# ltk-hall_main.net
KiCad netlist of a schematic drawn in Altium Designer
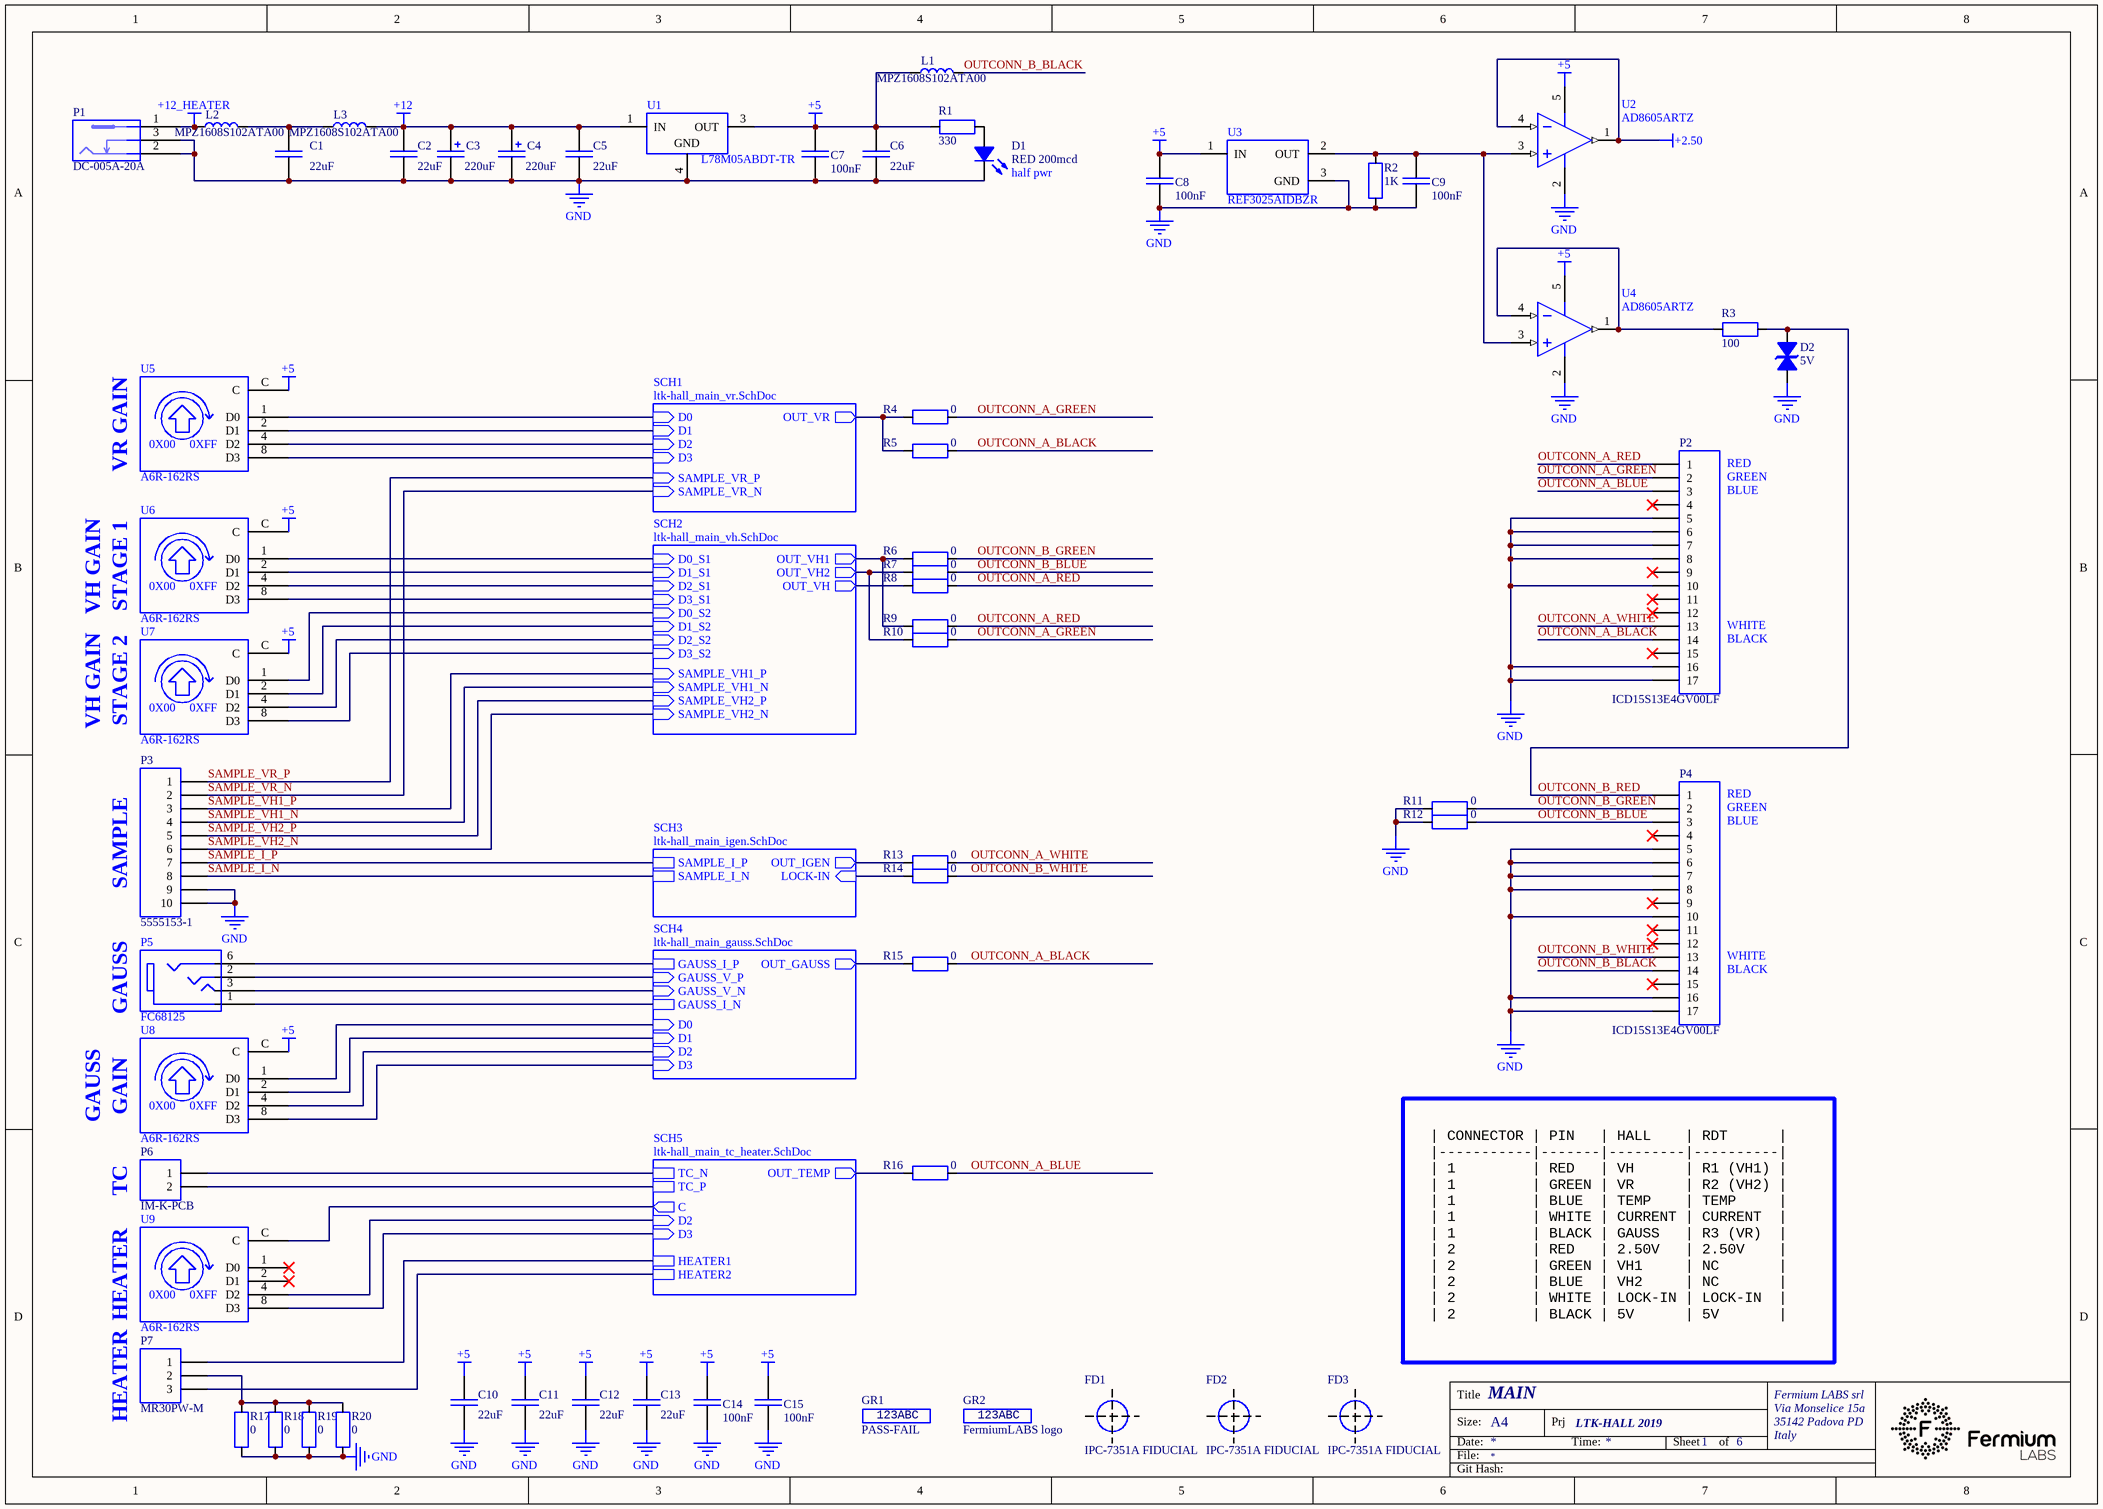
[diagram p0: ltk-hall_main.SchDoc]

(export (version "E")
  (design (tool "Eeschema 10.0.6"))
  (components
    (comp (ref "C1")
      (value "22uF")
      (footprint "CAP 0805_2012")
      (description "CAP SMD MLCC 22uF 25V 0805 X5R")
      (fields (field (name "PART NUMBER") "4e18e584-a077-4dfe-b9da-5e528e787323"))
      (libsource (lib "frmdblib") (part "GENERIC_C"))
    )
    (comp (ref "C2")
      (value "22uF")
      (footprint "CAP 0805_2012")
      (description "CAP SMD MLCC 22uF 25V 0805 X5R")
      (fields (field (name "PART NUMBER") "4e18e584-a077-4dfe-b9da-5e528e787323"))
      (libsource (lib "frmdblib") (part "GENERIC_C"))
    )
    (comp (ref "C3")
      (value "220uF")
      (footprint "3924B366-8672-45E9-B0BE-62DACC24E783")
      (description "CAP  THT ELEC 220uF 25V 20%")
      (fields (field (name "PART NUMBER") "1a28df19-6d3e-4a71-836c-f22920f8e8ab"))
      (libsource (lib "frmdblib") (part "GENERIC_C_ELEC"))
    )
    (comp (ref "C4")
      (value "220uF")
      (footprint "3924B366-8672-45E9-B0BE-62DACC24E783")
      (description "CAP  THT ELEC 220uF 25V 20%")
      (fields (field (name "PART NUMBER") "1a28df19-6d3e-4a71-836c-f22920f8e8ab"))
      (libsource (lib "frmdblib") (part "GENERIC_C_ELEC"))
    )
    (comp (ref "C5")
      (value "22uF")
      (footprint "CAP 0805_2012")
      (description "CAP SMD MLCC 22uF 25V 0805 X5R")
      (fields (field (name "PART NUMBER") "4e18e584-a077-4dfe-b9da-5e528e787323"))
      (libsource (lib "frmdblib") (part "GENERIC_C"))
    )
    (comp (ref "C6")
      (value "22uF")
      (footprint "CAP 0805_2012")
      (description "CAP SMD MLCC 22uF 25V 0805 X5R")
      (fields (field (name "PART NUMBER") "4e18e584-a077-4dfe-b9da-5e528e787323"))
      (libsource (lib "frmdblib") (part "GENERIC_C"))
    )
    (comp (ref "C7")
      (value "100nF")
      (footprint "CAP 0603_1608")
      (description "CAP SMD MLCC 100nF 25V 0603 X7R")
      (fields (field (name "PART NUMBER") "02841f84-ac15-41b5-9e17-915f8f067828"))
      (libsource (lib "frmdblib") (part "GENERIC_C"))
    )
    (comp (ref "C8")
      (value "100nF")
      (footprint "CAP 0603_1608")
      (description "CAP SMD MLCC 100nF 25V 0603 X7R")
      (fields (field (name "PART NUMBER") "02841f84-ac15-41b5-9e17-915f8f067828"))
      (libsource (lib "frmdblib") (part "GENERIC_C"))
    )
    (comp (ref "C9")
      (value "100nF")
      (footprint "CAP 0603_1608")
      (description "CAP SMD MLCC 100nF 25V 0603 X7R")
      (fields (field (name "PART NUMBER") "02841f84-ac15-41b5-9e17-915f8f067828"))
      (libsource (lib "frmdblib") (part "GENERIC_C"))
    )
    (comp (ref "C10")
      (value "22uF")
      (footprint "CAP 0805_2012")
      (description "CAP SMD MLCC 22uF 25V 0805 X5R")
      (fields (field (name "PART NUMBER") "4e18e584-a077-4dfe-b9da-5e528e787323"))
      (libsource (lib "frmdblib") (part "GENERIC_C"))
    )
    (comp (ref "C11")
      (value "22uF")
      (footprint "CAP 0805_2012")
      (description "CAP SMD MLCC 22uF 25V 0805 X5R")
      (fields (field (name "PART NUMBER") "4e18e584-a077-4dfe-b9da-5e528e787323"))
      (libsource (lib "frmdblib") (part "GENERIC_C"))
    )
    (comp (ref "C12")
      (value "22uF")
      (footprint "CAP 0805_2012")
      (description "CAP SMD MLCC 22uF 25V 0805 X5R")
      (fields (field (name "PART NUMBER") "4e18e584-a077-4dfe-b9da-5e528e787323"))
      (libsource (lib "frmdblib") (part "GENERIC_C"))
    )
    (comp (ref "C13")
      (value "22uF")
      (footprint "CAP 0805_2012")
      (description "CAP SMD MLCC 22uF 25V 0805 X5R")
      (fields (field (name "PART NUMBER") "4e18e584-a077-4dfe-b9da-5e528e787323"))
      (libsource (lib "frmdblib") (part "GENERIC_C"))
    )
    (comp (ref "C14")
      (value "100nF")
      (footprint "CAP 0603_1608")
      (description "CAP SMD MLCC 100nF 25V 0603 X7R")
      (fields (field (name "PART NUMBER") "02841f84-ac15-41b5-9e17-915f8f067828"))
      (libsource (lib "frmdblib") (part "GENERIC_C"))
    )
    (comp (ref "C15")
      (value "100nF")
      (footprint "CAP 0603_1608")
      (description "CAP SMD MLCC 100nF 25V 0603 X7R")
      (fields (field (name "PART NUMBER") "02841f84-ac15-41b5-9e17-915f8f067828"))
      (libsource (lib "frmdblib") (part "GENERIC_C"))
    )
    (comp (ref "D1")
      (value "RED 200mcd")
      (footprint "ED49B4F6-595F-4D62-96BB-D7184CAA9B94")
      (description "DIODE LED THT 5MM RED 200mcd")
      (fields (field (name "PART NUMBER") "c65ae3d2-9539-4634-8979-616a331b7494"))
      (libsource (lib "frmdblib") (part "GENERIC_D_LED"))
    )
    (comp (ref "D2")
      (value "5V")
      (footprint "SOD523F")
      (description "DIODE SMD TVS 5V BIDIRECTIONAL SOD-523")
      (fields (field (name "PART NUMBER") "daa58212-38e2-4326-a156-8e48058c46f1"))
      (libsource (lib "frmdblib") (part "GENERIC_D_TVS_BI"))
    )
    (comp (ref "FD1")
      (value "IPC-7351A FIDUCIAL")
      (footprint "FIDUCIAL-IPC-7351A")
      (description "GRAPHICS FIDUCIAL IPC-7351A")
      (fields (field (name "PART NUMBER") "19da4612-eb95-43bb-9984-553a52b2a224"))
      (libsource (lib "frmdblib") (part "GENERIC_FIDUCIAL"))
    )
    (comp (ref "FD2")
      (value "IPC-7351A FIDUCIAL")
      (footprint "FIDUCIAL-IPC-7351A")
      (description "GRAPHICS FIDUCIAL IPC-7351A")
      (fields (field (name "PART NUMBER") "19da4612-eb95-43bb-9984-553a52b2a224"))
      (libsource (lib "frmdblib") (part "GENERIC_FIDUCIAL"))
    )
    (comp (ref "FD3")
      (value "IPC-7351A FIDUCIAL")
      (footprint "FIDUCIAL-IPC-7351A")
      (description "GRAPHICS FIDUCIAL IPC-7351A")
      (fields (field (name "PART NUMBER") "19da4612-eb95-43bb-9984-553a52b2a224"))
      (libsource (lib "frmdblib") (part "GENERIC_FIDUCIAL"))
    )
    (comp (ref "GR1")
      (value "PASS-FAIL")
      (footprint "0B1556B7-A534-4801-B57D-01EFA34B1205")
      (description "GRAPHICS PASS-FAIL MARK")
      (fields (field (name "PART NUMBER") "d1abe19f-3fed-4f20-b2ed-afc0ffbc6628"))
      (libsource (lib "frmdblib") (part "GENERIC_GRAPHIC"))
    )
    (comp (ref "GR2")
      (value "FermiumLABS logo")
      (footprint "5394DE47-A0E8-4329-8464-7791B7C19310")
      (description "GRAPHICS LOGO FERMIUM LABS SRL")
      (fields (field (name "PART NUMBER") "50f8ea88-0034-49fe-a263-d8e97bc35e2f"))
      (libsource (lib "frmdblib") (part "GENERIC_GRAPHIC"))
    )
    (comp (ref "L1")
      (value "MPZ1608S102ATA00")
      (footprint "FER 0603_1608")
      (description "FER SMD CHIP 0603 800mA 1K@100MHz 300mOhm")
      (fields (field (name "PART NUMBER") "a4b2e015-bf25-47b8-954c-a5b040744a3a"))
      (libsource (lib "frmdblib") (part "GENERIC_L"))
    )
    (comp (ref "L2")
      (value "MPZ1608S102ATA00")
      (footprint "FER 0603_1608")
      (description "FER SMD CHIP 0603 800mA 1K@100MHz 300mOhm")
      (fields (field (name "PART NUMBER") "a4b2e015-bf25-47b8-954c-a5b040744a3a"))
      (libsource (lib "frmdblib") (part "GENERIC_L"))
    )
    (comp (ref "L3")
      (value "MPZ1608S102ATA00")
      (footprint "FER 0603_1608")
      (description "FER SMD CHIP 0603 800mA 1K@100MHz 300mOhm")
      (fields (field (name "PART NUMBER") "a4b2e015-bf25-47b8-954c-a5b040744a3a"))
      (libsource (lib "frmdblib") (part "GENERIC_L"))
    )
    (comp (ref "P1")
      (value "DC-005A-20A")
      (footprint "F0972D8A-C5C0-4A84-836D-A9666EE65C2D")
      (description "CONN THT DC JACK 0.5A 30VDC 5Kcycles")
      (fields (field (name "PART NUMBER") "b53db51a-1725-412b-9039-fa7a45c7c438"))
      (libsource (lib "frmdblib") (part "34A1CD0B-E262-46EF-B9F1-39CB809C308F"))
    )
    (comp (ref "P2")
      (value "ICD15S13E4GV00LF")
      (footprint "66D8AC91-DC10-42D3-BF25-693004815827")
      (description "CONN D-SUB HD 15POLES BLACK THT")
      (fields (field (name "PART NUMBER") "af155709-b835-40ac-b9b5-4a44b0fd2777"))
      (libsource (lib "frmdblib") (part "Header 17"))
    )
    (comp (ref "P3")
      (value "5555153-1")
      (footprint "03FA2727-72E9-446E-856D-3DD573B1EBDD")
      (description "CONN RJ45 SHIELDED")
      (fields (field (name "PART NUMBER") "f401b84a-9695-45b1-951e-00bef0039069"))
      (libsource (lib "frmdblib") (part "Header 10"))
    )
    (comp (ref "P4")
      (value "ICD15S13E4GV00LF")
      (footprint "66D8AC91-DC10-42D3-BF25-693004815827")
      (description "CONN D-SUB HD 15POLES BLACK THT")
      (fields (field (name "PART NUMBER") "af155709-b835-40ac-b9b5-4a44b0fd2777"))
      (libsource (lib "frmdblib") (part "Header 17"))
    )
    (comp (ref "P5")
      (value "FC68125")
      (footprint "977BFFC7-4CFC-4119-A8B4-AB88E5A1DB2B")
      (description "CONN JACK 3.5MM 4POLE THT")
      (fields (field (name "PART NUMBER") "3e3c57e9-f1b8-4c12-8bb1-97da9eb9c220"))
      (libsource (lib "frmdblib") (part "A6099F20-3616-40CA-8CCB-374681413BA7"))
    )
    (comp (ref "P6")
      (value "IM-K-PCB")
      (footprint "9044FB30-693E-4780-9B0B-95C5421D70E8")
      (description "CONN THERMOCOUPLE K-TYPE THT")
      (fields (field (name "PART NUMBER") "44088476-53fa-4578-a611-1fd63affe7b4"))
      (libsource (lib "frmdblib") (part "Header 2"))
    )
    (comp (ref "P7")
      (value "MR30PW-M")
      (footprint "B3F23392-877C-4EEC-B1AF-B260E8D92153")
      (description "CONN DC 3 POLE 15A PCB MALE")
      (fields (field (name "PART NUMBER") "8565bfd1-7a71-455a-a363-4ce9dda60de6"))
      (libsource (lib "frmdblib") (part "Header 3"))
    )
    (comp (ref "R1")
      (value "330")
      (footprint "RES 0603_1608")
      (description "RES SMD 330 OHM 1% 1/10W 0603")
      (fields (field (name "PART NUMBER") "e8555d7b-eeda-4727-b2e1-550cdc03d819"))
      (libsource (lib "frmdblib") (part "GENERIC_R"))
    )
    (comp (ref "R2")
      (value "1K")
      (footprint "RES 0603_1608")
      (description "RES SMD 1K OHM 1% 1/10W 0603")
      (fields (field (name "PART NUMBER") "a678220f-9e9d-4863-a833-9993504f723c"))
      (libsource (lib "frmdblib") (part "GENERIC_R"))
    )
    (comp (ref "R3")
      (value "100")
      (footprint "RES 0603_1608")
      (description "RES SMD 100 OHM 1% 1/10W 0603")
      (fields (field (name "PART NUMBER") "0a6c4b74-f837-4563-b154-6e196d753525"))
      (libsource (lib "frmdblib") (part "GENERIC_R"))
    )
    (comp (ref "R4")
      (value "0")
      (footprint "RES 0603_1608")
      (description "RES SMD 0 OHM 5% 1/10W 0603")
      (fields (field (name "PART NUMBER") "6ae227f9-847f-4766-8522-e11a83531204"))
      (libsource (lib "frmdblib") (part "GENERIC_R"))
    )
    (comp (ref "R5")
      (value "0")
      (footprint "RES 0603_1608")
      (description "RES SMD 0 OHM 5% 1/10W 0603")
      (fields (field (name "PART NUMBER") "6ae227f9-847f-4766-8522-e11a83531204"))
      (libsource (lib "frmdblib") (part "GENERIC_R"))
    )
    (comp (ref "R6")
      (value "0")
      (footprint "RES 0603_1608")
      (description "RES SMD 0 OHM 5% 1/10W 0603")
      (fields (field (name "PART NUMBER") "6ae227f9-847f-4766-8522-e11a83531204"))
      (libsource (lib "frmdblib") (part "GENERIC_R"))
    )
    (comp (ref "R7")
      (value "0")
      (footprint "RES 0603_1608")
      (description "RES SMD 0 OHM 5% 1/10W 0603")
      (fields (field (name "PART NUMBER") "6ae227f9-847f-4766-8522-e11a83531204"))
      (libsource (lib "frmdblib") (part "GENERIC_R"))
    )
    (comp (ref "R8")
      (value "0")
      (footprint "RES 0603_1608")
      (description "RES SMD 0 OHM 5% 1/10W 0603")
      (fields (field (name "PART NUMBER") "6ae227f9-847f-4766-8522-e11a83531204"))
      (libsource (lib "frmdblib") (part "GENERIC_R"))
    )
    (comp (ref "R9")
      (value "0")
      (footprint "RES 0603_1608")
      (description "RES SMD 0 OHM 5% 1/10W 0603")
      (fields (field (name "PART NUMBER") "6ae227f9-847f-4766-8522-e11a83531204"))
      (libsource (lib "frmdblib") (part "GENERIC_R"))
    )
    (comp (ref "R10")
      (value "0")
      (footprint "RES 0603_1608")
      (description "RES SMD 0 OHM 5% 1/10W 0603")
      (fields (field (name "PART NUMBER") "6ae227f9-847f-4766-8522-e11a83531204"))
      (libsource (lib "frmdblib") (part "GENERIC_R"))
    )
    (comp (ref "R11")
      (value "0")
      (footprint "RES 0603_1608")
      (description "RES SMD 0 OHM 5% 1/10W 0603")
      (fields (field (name "PART NUMBER") "6ae227f9-847f-4766-8522-e11a83531204"))
      (libsource (lib "frmdblib") (part "GENERIC_R"))
    )
    (comp (ref "R12")
      (value "0")
      (footprint "RES 0603_1608")
      (description "RES SMD 0 OHM 5% 1/10W 0603")
      (fields (field (name "PART NUMBER") "6ae227f9-847f-4766-8522-e11a83531204"))
      (libsource (lib "frmdblib") (part "GENERIC_R"))
    )
    (comp (ref "R13")
      (value "0")
      (footprint "RES 0603_1608")
      (description "RES SMD 0 OHM 5% 1/10W 0603")
      (fields (field (name "PART NUMBER") "6ae227f9-847f-4766-8522-e11a83531204"))
      (libsource (lib "frmdblib") (part "GENERIC_R"))
    )
    (comp (ref "R14")
      (value "0")
      (footprint "RES 0603_1608")
      (description "RES SMD 0 OHM 5% 1/10W 0603")
      (fields (field (name "PART NUMBER") "6ae227f9-847f-4766-8522-e11a83531204"))
      (libsource (lib "frmdblib") (part "GENERIC_R"))
    )
    (comp (ref "R15")
      (value "0")
      (footprint "RES 0603_1608")
      (description "RES SMD 0 OHM 5% 1/10W 0603")
      (fields (field (name "PART NUMBER") "6ae227f9-847f-4766-8522-e11a83531204"))
      (libsource (lib "frmdblib") (part "GENERIC_R"))
    )
    (comp (ref "R16")
      (value "0")
      (footprint "RES 0603_1608")
      (description "RES SMD 0 OHM 5% 1/10W 0603")
      (fields (field (name "PART NUMBER") "6ae227f9-847f-4766-8522-e11a83531204"))
      (libsource (lib "frmdblib") (part "GENERIC_R"))
    )
    (comp (ref "R17")
      (value "0")
      (footprint "RES 0603_1608")
      (description "RES SMD 0 OHM 5% 1/10W 0603")
      (fields (field (name "PART NUMBER") "6ae227f9-847f-4766-8522-e11a83531204"))
      (libsource (lib "frmdblib") (part "GENERIC_R"))
    )
    (comp (ref "R18")
      (value "0")
      (footprint "RES 0603_1608")
      (description "RES SMD 0 OHM 5% 1/10W 0603")
      (fields (field (name "PART NUMBER") "6ae227f9-847f-4766-8522-e11a83531204"))
      (libsource (lib "frmdblib") (part "GENERIC_R"))
    )
    (comp (ref "R19")
      (value "0")
      (footprint "RES 0603_1608")
      (description "RES SMD 0 OHM 5% 1/10W 0603")
      (fields (field (name "PART NUMBER") "6ae227f9-847f-4766-8522-e11a83531204"))
      (libsource (lib "frmdblib") (part "GENERIC_R"))
    )
    (comp (ref "R20")
      (value "0")
      (footprint "RES 0603_1608")
      (description "RES SMD 0 OHM 5% 1/10W 0603")
      (fields (field (name "PART NUMBER") "6ae227f9-847f-4766-8522-e11a83531204"))
      (libsource (lib "frmdblib") (part "GENERIC_R"))
    )
    (comp (ref "U1")
      (value "L78M05ABDT-TR")
      (footprint "4BDA507D-BB70-4009-B963-85AD90086B51")
      (description "IC SMD LINEAR VOLTAGE REGULATOR 5V 500mA DPAK/TO-252")
      (fields (field (name "PART NUMBER") "446536aa-1bdd-4764-8cae-49f4e0c126ff"))
      (libsource (lib "frmdblib") (part "568C7F7F-B71D-457E-B5FB-AE9D42DA8928"))
    )
    (comp (ref "U2")
      (value "AD8605ARTZ")
      (footprint "A3DDA0BC-073E-4B18-9613-F713A7EC1E27")
      (description "IC OPAMP 65uV 1pA RRIO 5V 80mA SOT-23-5")
      (fields (field (name "PART NUMBER") "5610e9ea-bca8-49b2-8e5f-11409231f6a4"))
      (libsource (lib "frmdblib") (part "8096D751-9DCE-401B-B65E-AAEE0733EA70"))
    )
    (comp (ref "U3")
      (value "REF3025AIDBZR")
      (footprint "TI SOT-23-3 DBZ")
      (description "IC VOLTAGE REF SERIES 2.5V 75ppm 0.2% SOT-23")
      (fields (field (name "PART NUMBER") "0de0df07-6dfd-42d8-9fe7-171c27772811"))
      (libsource (lib "frmdblib") (part "7CD2CEE0-4EC4-4AB4-93FF-624CFED04EB7"))
    )
    (comp (ref "U4")
      (value "AD8605ARTZ")
      (footprint "A3DDA0BC-073E-4B18-9613-F713A7EC1E27")
      (description "IC OPAMP 65uV 1pA RRIO 5V 80mA SOT-23-5")
      (fields (field (name "PART NUMBER") "5610e9ea-bca8-49b2-8e5f-11409231f6a4"))
      (libsource (lib "frmdblib") (part "8096D751-9DCE-401B-B65E-AAEE0733EA70"))
    )
    (comp (ref "U5")
      (value "A6R-162RS")
      (footprint "2599C238-5645-4A8C-8BF9-C7515FACCFA0")
      (description "SWITCH ROTARY HEX/BCD 16 POSITIONS")
      (fields (field (name "PART NUMBER") "bbf157ad-cd7a-4e82-97e3-d6a037590888"))
      (libsource (lib "frmdblib") (part "EFC705A0-D700-486A-81AB-6EE045EE6C24"))
    )
    (comp (ref "U6")
      (value "A6R-162RS")
      (footprint "2599C238-5645-4A8C-8BF9-C7515FACCFA0")
      (description "SWITCH ROTARY HEX/BCD 16 POSITIONS")
      (fields (field (name "PART NUMBER") "bbf157ad-cd7a-4e82-97e3-d6a037590888"))
      (libsource (lib "frmdblib") (part "EFC705A0-D700-486A-81AB-6EE045EE6C24"))
    )
    (comp (ref "U7")
      (value "A6R-162RS")
      (footprint "2599C238-5645-4A8C-8BF9-C7515FACCFA0")
      (description "SWITCH ROTARY HEX/BCD 16 POSITIONS")
      (fields (field (name "PART NUMBER") "bbf157ad-cd7a-4e82-97e3-d6a037590888"))
      (libsource (lib "frmdblib") (part "EFC705A0-D700-486A-81AB-6EE045EE6C24"))
    )
    (comp (ref "U8")
      (value "A6R-162RS")
      (footprint "2599C238-5645-4A8C-8BF9-C7515FACCFA0")
      (description "SWITCH ROTARY HEX/BCD 16 POSITIONS")
      (fields (field (name "PART NUMBER") "bbf157ad-cd7a-4e82-97e3-d6a037590888"))
      (libsource (lib "frmdblib") (part "EFC705A0-D700-486A-81AB-6EE045EE6C24"))
    )
    (comp (ref "U9")
      (value "A6R-162RS")
      (footprint "2599C238-5645-4A8C-8BF9-C7515FACCFA0")
      (description "SWITCH ROTARY HEX/BCD 16 POSITIONS")
      (fields (field (name "PART NUMBER") "bbf157ad-cd7a-4e82-97e3-d6a037590888"))
      (libsource (lib "frmdblib") (part "EFC705A0-D700-486A-81AB-6EE045EE6C24"))
    )
  )
  (nets
    (net (code "1") (name "+2.50") (class "Default")
      (node (ref "U2") (pin "1") (pinfunction "OUT_1") (pintype "output"))
      (node (ref "U2") (pin "4") (pinfunction "-IN_4") (pintype "input"))
    )
    (net (code "2") (name "+5") (class "Default")
      (node (ref "C10") (pin "1") (pintype "passive"))
      (node (ref "C11") (pin "1") (pintype "passive"))
      (node (ref "C12") (pin "1") (pintype "passive"))
      (node (ref "C13") (pin "1") (pintype "passive"))
      (node (ref "C14") (pin "1") (pintype "passive"))
      (node (ref "C15") (pin "1") (pintype "passive"))
      (node (ref "C6") (pin "1") (pintype "passive"))
      (node (ref "C7") (pin "1") (pintype "passive"))
      (node (ref "C8") (pin "1") (pintype "passive"))
      (node (ref "L1") (pin "1") (pintype "passive"))
      (node (ref "R1") (pin "1") (pintype "passive"))
      (node (ref "U1") (pin "3") (pinfunction "OUT_3") (pintype "power_in"))
      (node (ref "U2") (pin "5") (pinfunction "+V_5") (pintype "power_in"))
      (node (ref "U3") (pin "1") (pinfunction "IN_1") (pintype "power_in"))
      (node (ref "U4") (pin "5") (pinfunction "+V_5") (pintype "power_in"))
      (node (ref "U5") (pin "C") (pinfunction "C_C") (pintype "passive"))
      (node (ref "U6") (pin "C") (pinfunction "C_C") (pintype "passive"))
      (node (ref "U7") (pin "C") (pinfunction "C_C") (pintype "passive"))
      (node (ref "U8") (pin "C") (pinfunction "C_C") (pintype "passive"))
    )
    (net (code "3") (name "+12") (class "Default")
      (node (ref "C2") (pin "1") (pintype "passive"))
      (node (ref "C3") (pin "1") (pintype "passive"))
      (node (ref "C4") (pin "1") (pintype "passive"))
      (node (ref "C5") (pin "1") (pintype "passive"))
      (node (ref "L3") (pin "2") (pintype "passive"))
      (node (ref "U1") (pin "1") (pinfunction "IN_1") (pintype "power_in"))
    )
    (net (code "4") (name "+12_HEATER") (class "Default")
      (node (ref "L2") (pin "1") (pintype "passive"))
      (node (ref "P1") (pin "1") (pinfunction "1_1") (pintype "passive"))
    )
    (net (code "5") (name "/C") (class "Default")
      (node (ref "U9") (pin "C") (pinfunction "C_C") (pintype "passive"))
    )
    (net (code "6") (name "/D0") (class "Default")
      (node (ref "U8") (pin "1") (pinfunction "D0_1") (pintype "passive"))
    )
    (net (code "7") (name "/D0_1") (class "Default")
      (node (ref "U5") (pin "1") (pinfunction "D0_1") (pintype "passive"))
    )
    (net (code "8") (name "/D0_S1") (class "Default")
      (node (ref "U6") (pin "1") (pinfunction "D0_1") (pintype "passive"))
    )
    (net (code "9") (name "/D0_S2") (class "Default")
      (node (ref "U7") (pin "1") (pinfunction "D0_1") (pintype "passive"))
    )
    (net (code "10") (name "/D1") (class "Default")
      (node (ref "U8") (pin "2") (pinfunction "D1_2") (pintype "passive"))
    )
    (net (code "11") (name "/D1_1") (class "Default")
      (node (ref "U5") (pin "2") (pinfunction "D1_2") (pintype "passive"))
    )
    (net (code "12") (name "/D1_S1") (class "Default")
      (node (ref "U6") (pin "2") (pinfunction "D1_2") (pintype "passive"))
    )
    (net (code "13") (name "/D1_S2") (class "Default")
      (node (ref "U7") (pin "2") (pinfunction "D1_2") (pintype "passive"))
    )
    (net (code "14") (name "/D2") (class "Default")
      (node (ref "U9") (pin "4") (pinfunction "D2_4") (pintype "passive"))
    )
    (net (code "15") (name "/D2_1") (class "Default")
      (node (ref "U5") (pin "4") (pinfunction "D2_4") (pintype "passive"))
    )
    (net (code "16") (name "/D2_2") (class "Default")
      (node (ref "U8") (pin "4") (pinfunction "D2_4") (pintype "passive"))
    )
    (net (code "17") (name "/D2_S1") (class "Default")
      (node (ref "U6") (pin "4") (pinfunction "D2_4") (pintype "passive"))
    )
    (net (code "18") (name "/D2_S2") (class "Default")
      (node (ref "U7") (pin "4") (pinfunction "D2_4") (pintype "passive"))
    )
    (net (code "19") (name "/D3") (class "Default")
      (node (ref "U9") (pin "8") (pinfunction "D3_8") (pintype "passive"))
    )
    (net (code "20") (name "/D3_1") (class "Default")
      (node (ref "U5") (pin "8") (pinfunction "D3_8") (pintype "passive"))
    )
    (net (code "21") (name "/D3_2") (class "Default")
      (node (ref "U8") (pin "8") (pinfunction "D3_8") (pintype "passive"))
    )
    (net (code "22") (name "/D3_S1") (class "Default")
      (node (ref "U6") (pin "8") (pinfunction "D3_8") (pintype "passive"))
    )
    (net (code "23") (name "/D3_S2") (class "Default")
      (node (ref "U7") (pin "8") (pinfunction "D3_8") (pintype "passive"))
    )
    (net (code "24") (name "/GAUSS_I_N") (class "Default")
      (node (ref "P5") (pin "1") (pinfunction "1_1") (pintype "passive"))
    )
    (net (code "25") (name "/GAUSS_I_P") (class "Default")
      (node (ref "P5") (pin "6") (pinfunction "6_6") (pintype "passive"))
    )
    (net (code "26") (name "/GAUSS_V_N") (class "Default")
      (node (ref "P5") (pin "3") (pinfunction "3_3") (pintype "passive"))
    )
    (net (code "27") (name "/GAUSS_V_P") (class "Default")
      (node (ref "P5") (pin "2") (pinfunction "2_2") (pintype "passive"))
    )
    (net (code "28") (name "/HEATER1") (class "Default")
      (node (ref "P7") (pin "1") (pinfunction "1_1") (pintype "passive"))
    )
    (net (code "29") (name "/HEATER2") (class "Default")
      (node (ref "P7") (pin "3") (pinfunction "3_3") (pintype "passive"))
    )
    (net (code "30") (name "/LOCK-IN") (class "Default") (node (ref "R14") (pin "1") (pintype "passive")))
    (net (code "31") (name "/OUTCONN_A_BLACK") (class "Default")
      (node (ref "P2") (pin "14") (pinfunction "14_14") (pintype "passive"))
      (node (ref "R15") (pin "2") (pintype "passive"))
      (node (ref "R5") (pin "2") (pintype "passive"))
    )
    (net (code "32") (name "/OUTCONN_A_BLUE") (class "Default")
      (node (ref "P2") (pin "3") (pinfunction "3_3") (pintype "passive"))
      (node (ref "R16") (pin "2") (pintype "passive"))
    )
    (net (code "33") (name "/OUTCONN_A_GREEN") (class "Default")
      (node (ref "P2") (pin "2") (pinfunction "2_2") (pintype "passive"))
      (node (ref "R10") (pin "2") (pintype "passive"))
      (node (ref "R4") (pin "2") (pintype "passive"))
    )
    (net (code "34") (name "/OUTCONN_A_RED") (class "Default")
      (node (ref "P2") (pin "1") (pinfunction "1_1") (pintype "passive"))
      (node (ref "R8") (pin "2") (pintype "passive"))
      (node (ref "R9") (pin "2") (pintype "passive"))
    )
    (net (code "35") (name "/OUTCONN_A_WHITE") (class "Default")
      (node (ref "P2") (pin "13") (pinfunction "13_13") (pintype "passive"))
      (node (ref "R13") (pin "2") (pintype "passive"))
    )
    (net (code "36") (name "/OUTCONN_B_BLACK") (class "Default")
      (node (ref "L1") (pin "2") (pintype "passive"))
      (node (ref "P4") (pin "14") (pinfunction "14_14") (pintype "passive"))
    )
    (net (code "37") (name "/OUTCONN_B_BLUE") (class "Default")
      (node (ref "P4") (pin "3") (pinfunction "3_3") (pintype "passive"))
      (node (ref "R12") (pin "2") (pintype "passive"))
      (node (ref "R7") (pin "2") (pintype "passive"))
    )
    (net (code "38") (name "/OUTCONN_B_GREEN") (class "Default")
      (node (ref "P4") (pin "2") (pinfunction "2_2") (pintype "passive"))
      (node (ref "R11") (pin "2") (pintype "passive"))
      (node (ref "R6") (pin "2") (pintype "passive"))
    )
    (net (code "39") (name "/OUTCONN_B_RED") (class "Default")
      (node (ref "D2") (pin "1") (pintype "passive"))
      (node (ref "P4") (pin "1") (pinfunction "1_1") (pintype "passive"))
      (node (ref "R3") (pin "2") (pintype "passive"))
    )
    (net (code "40") (name "/OUTCONN_B_WHITE") (class "Default")
      (node (ref "P4") (pin "13") (pinfunction "13_13") (pintype "passive"))
      (node (ref "R14") (pin "2") (pintype "passive"))
    )
    (net (code "41") (name "/OUT_GAUSS") (class "Default") (node (ref "R15") (pin "1") (pintype "passive")))
    (net (code "42") (name "/OUT_IGEN") (class "Default") (node (ref "R13") (pin "1") (pintype "passive")))
    (net (code "43") (name "/OUT_TEMP") (class "Default") (node (ref "R16") (pin "1") (pintype "passive")))
    (net (code "44") (name "/OUT_VH") (class "Default") (node (ref "R8") (pin "1") (pintype "passive")))
    (net (code "45") (name "/OUT_VH1") (class "Default")
      (node (ref "R6") (pin "1") (pintype "passive"))
      (node (ref "R9") (pin "1") (pintype "passive"))
    )
    (net (code "46") (name "/OUT_VH2") (class "Default")
      (node (ref "R10") (pin "1") (pintype "passive"))
      (node (ref "R7") (pin "1") (pintype "passive"))
    )
    (net (code "47") (name "/OUT_VR") (class "Default")
      (node (ref "R4") (pin "1") (pintype "passive"))
      (node (ref "R5") (pin "1") (pintype "passive"))
    )
    (net (code "48") (name "/SAMPLE_I_N") (class "Default")
      (node (ref "P3") (pin "8") (pinfunction "8_8") (pintype "passive"))
    )
    (net (code "49") (name "/SAMPLE_I_P") (class "Default")
      (node (ref "P3") (pin "7") (pinfunction "7_7") (pintype "passive"))
    )
    (net (code "50") (name "/SAMPLE_VH1_N") (class "Default")
      (node (ref "P3") (pin "4") (pinfunction "4_4") (pintype "passive"))
    )
    (net (code "51") (name "/SAMPLE_VH1_P") (class "Default")
      (node (ref "P3") (pin "3") (pinfunction "3_3") (pintype "passive"))
    )
    (net (code "52") (name "/SAMPLE_VH2_N") (class "Default")
      (node (ref "P3") (pin "6") (pinfunction "6_6") (pintype "passive"))
    )
    (net (code "53") (name "/SAMPLE_VH2_P") (class "Default")
      (node (ref "P3") (pin "5") (pinfunction "5_5") (pintype "passive"))
    )
    (net (code "54") (name "/SAMPLE_VR_N") (class "Default")
      (node (ref "P3") (pin "2") (pinfunction "2_2") (pintype "passive"))
    )
    (net (code "55") (name "/SAMPLE_VR_P") (class "Default")
      (node (ref "P3") (pin "1") (pinfunction "1_1") (pintype "passive"))
    )
    (net (code "56") (name "/TC_N") (class "Default")
      (node (ref "P6") (pin "1") (pinfunction "1_1") (pintype "passive"))
    )
    (net (code "57") (name "/TC_P") (class "Default")
      (node (ref "P6") (pin "2") (pinfunction "2_2") (pintype "passive"))
    )
    (net (code "58") (name "GND") (class "Default")
      (node (ref "C1") (pin "2") (pintype "passive"))
      (node (ref "C10") (pin "2") (pintype "passive"))
      (node (ref "C11") (pin "2") (pintype "passive"))
      (node (ref "C12") (pin "2") (pintype "passive"))
      (node (ref "C13") (pin "2") (pintype "passive"))
      (node (ref "C14") (pin "2") (pintype "passive"))
      (node (ref "C15") (pin "2") (pintype "passive"))
      (node (ref "C2") (pin "2") (pintype "passive"))
      (node (ref "C3") (pin "2") (pintype "passive"))
      (node (ref "C4") (pin "2") (pintype "passive"))
      (node (ref "C5") (pin "2") (pintype "passive"))
      (node (ref "C6") (pin "2") (pintype "passive"))
      (node (ref "C7") (pin "2") (pintype "passive"))
      (node (ref "C8") (pin "2") (pintype "passive"))
      (node (ref "C9") (pin "2") (pintype "passive"))
      (node (ref "D1") (pin "1") (pinfunction "K_1") (pintype "passive"))
      (node (ref "D2") (pin "2") (pintype "passive"))
      (node (ref "P1") (pin "2") (pinfunction "2_2") (pintype "passive"))
      (node (ref "P1") (pin "3") (pinfunction "3_3") (pintype "passive"))
      (node (ref "P2") (pin "10") (pinfunction "10_10") (pintype "passive"))
      (node (ref "P2") (pin "16") (pinfunction "16_16") (pintype "passive"))
      (node (ref "P2") (pin "17") (pinfunction "17_17") (pintype "passive"))
      (node (ref "P2") (pin "5") (pinfunction "5_5") (pintype "passive"))
      (node (ref "P2") (pin "6") (pinfunction "6_6") (pintype "passive"))
      (node (ref "P2") (pin "7") (pinfunction "7_7") (pintype "passive"))
      (node (ref "P2") (pin "8") (pinfunction "8_8") (pintype "passive"))
      (node (ref "P3") (pin "10") (pinfunction "10_10") (pintype "passive"))
      (node (ref "P3") (pin "9") (pinfunction "9_9") (pintype "passive"))
      (node (ref "P4") (pin "10") (pinfunction "10_10") (pintype "passive"))
      (node (ref "P4") (pin "16") (pinfunction "16_16") (pintype "passive"))
      (node (ref "P4") (pin "17") (pinfunction "17_17") (pintype "passive"))
      (node (ref "P4") (pin "5") (pinfunction "5_5") (pintype "passive"))
      (node (ref "P4") (pin "6") (pinfunction "6_6") (pintype "passive"))
      (node (ref "P4") (pin "7") (pinfunction "7_7") (pintype "passive"))
      (node (ref "P4") (pin "8") (pinfunction "8_8") (pintype "passive"))
      (node (ref "R11") (pin "1") (pintype "passive"))
      (node (ref "R12") (pin "1") (pintype "passive"))
      (node (ref "R17") (pin "1") (pintype "passive"))
      (node (ref "R18") (pin "1") (pintype "passive"))
      (node (ref "R19") (pin "1") (pintype "passive"))
      (node (ref "R2") (pin "1") (pintype "passive"))
      (node (ref "R20") (pin "1") (pintype "passive"))
      (node (ref "U1") (pin "4") (pinfunction "GND_4") (pintype "power_in"))
      (node (ref "U2") (pin "2") (pinfunction "-V_2") (pintype "power_in"))
      (node (ref "U3") (pin "3") (pinfunction "GND_3") (pintype "power_in"))
      (node (ref "U4") (pin "2") (pinfunction "-V_2") (pintype "power_in"))
    )
    (net (code "59") (name "Net-(C1-Pad1)") (class "Default")
      (node (ref "C1") (pin "1") (pintype "passive"))
      (node (ref "L2") (pin "2") (pintype "passive"))
      (node (ref "L3") (pin "1") (pintype "passive"))
    )
    (net (code "60") (name "Net-(D1-A)") (class "Default")
      (node (ref "D1") (pin "2") (pinfunction "A_2") (pintype "passive"))
      (node (ref "R1") (pin "2") (pintype "passive"))
    )
    (net (code "61") (name "Net-(P7-Pad2)") (class "Default")
      (node (ref "P7") (pin "2") (pinfunction "2_2") (pintype "passive"))
      (node (ref "R17") (pin "2") (pintype "passive"))
      (node (ref "R18") (pin "2") (pintype "passive"))
      (node (ref "R19") (pin "2") (pintype "passive"))
      (node (ref "R20") (pin "2") (pintype "passive"))
    )
    (net (code "62") (name "Net-(U2-+IN)") (class "Default")
      (node (ref "C9") (pin "1") (pintype "passive"))
      (node (ref "R2") (pin "2") (pintype "passive"))
      (node (ref "U2") (pin "3") (pinfunction "+IN_3") (pintype "input"))
      (node (ref "U3") (pin "2") (pinfunction "OUT_2") (pintype "power_in"))
      (node (ref "U4") (pin "3") (pinfunction "+IN_3") (pintype "input"))
    )
    (net (code "63") (name "Net-(U4--IN)") (class "Default")
      (node (ref "R3") (pin "1") (pintype "passive"))
      (node (ref "U4") (pin "1") (pinfunction "OUT_1") (pintype "output"))
      (node (ref "U4") (pin "4") (pinfunction "-IN_4") (pintype "input"))
    )
    (net (code "64") (name "unconnected-(P2-Pad4)") (class "Default")
      (node (ref "P2") (pin "4") (pinfunction "4_4") (pintype "passive+no_connect"))
    )
    (net (code "65") (name "unconnected-(P2-Pad9)") (class "Default")
      (node (ref "P2") (pin "9") (pinfunction "9_9") (pintype "passive+no_connect"))
    )
    (net (code "66") (name "unconnected-(P2-Pad11)") (class "Default")
      (node (ref "P2") (pin "11") (pinfunction "11_11") (pintype "passive+no_connect"))
    )
    (net (code "67") (name "unconnected-(P2-Pad12)") (class "Default")
      (node (ref "P2") (pin "12") (pinfunction "12_12") (pintype "passive+no_connect"))
    )
    (net (code "68") (name "unconnected-(P2-Pad15)") (class "Default")
      (node (ref "P2") (pin "15") (pinfunction "15_15") (pintype "passive+no_connect"))
    )
    (net (code "69") (name "unconnected-(P4-Pad4)") (class "Default")
      (node (ref "P4") (pin "4") (pinfunction "4_4") (pintype "passive+no_connect"))
    )
    (net (code "70") (name "unconnected-(P4-Pad9)") (class "Default")
      (node (ref "P4") (pin "9") (pinfunction "9_9") (pintype "passive+no_connect"))
    )
    (net (code "71") (name "unconnected-(P4-Pad11)") (class "Default")
      (node (ref "P4") (pin "11") (pinfunction "11_11") (pintype "passive+no_connect"))
    )
    (net (code "72") (name "unconnected-(P4-Pad12)") (class "Default")
      (node (ref "P4") (pin "12") (pinfunction "12_12") (pintype "passive+no_connect"))
    )
    (net (code "73") (name "unconnected-(P4-Pad15)") (class "Default")
      (node (ref "P4") (pin "15") (pinfunction "15_15") (pintype "passive+no_connect"))
    )
    (net (code "74") (name "unconnected-(U9-D0-Pad1)") (class "Default")
      (node (ref "U9") (pin "1") (pinfunction "D0_1") (pintype "passive+no_connect"))
    )
    (net (code "75") (name "unconnected-(U9-D1-Pad2)") (class "Default")
      (node (ref "U9") (pin "2") (pinfunction "D1_2") (pintype "passive+no_connect"))
    )
  )
)
